# Silicoin.net
KiCad netlist of a schematic drawn in EAGLE
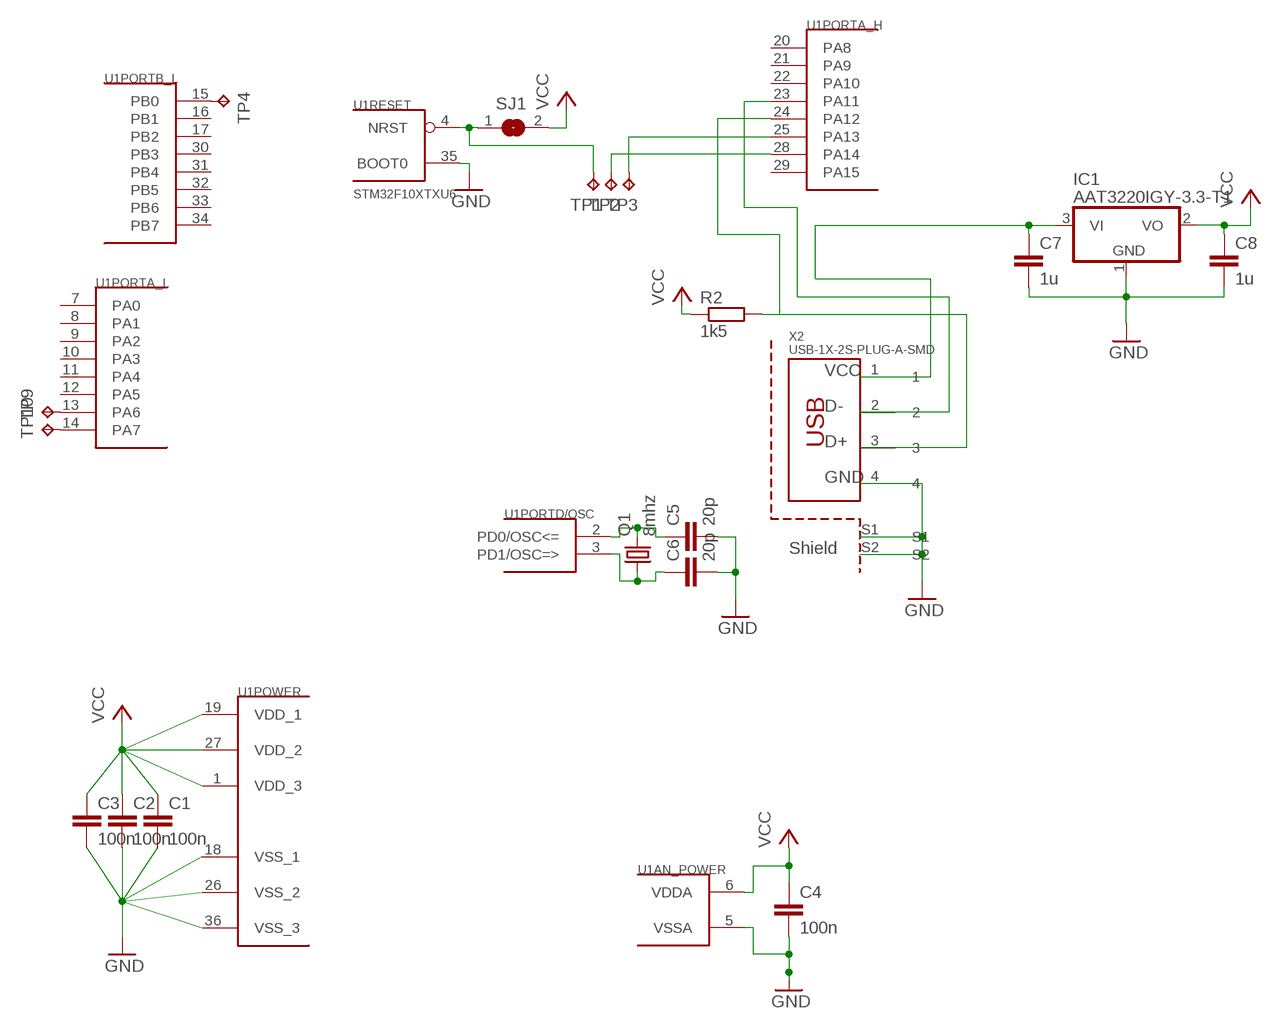
[diagram p0: schematic, sheet 1]

(export (version "E")
  (design (tool "Eeschema 10.0.6"))
  (components
    (comp (ref "C1")
      (value "100n")
      (footprint "eagle-import:C0603")
      (libsource (lib "eagle-import") (part "C-EUC0603"))
    )
    (comp (ref "C2")
      (value "100n")
      (footprint "eagle-import:C0603")
      (libsource (lib "eagle-import") (part "C-EUC0603"))
    )
    (comp (ref "C3")
      (value "100n")
      (footprint "eagle-import:C0603")
      (libsource (lib "eagle-import") (part "C-EUC0603"))
    )
    (comp (ref "C4")
      (value "100n")
      (footprint "eagle-import:C0603")
      (libsource (lib "eagle-import") (part "C-EUC0603"))
    )
    (comp (ref "C5")
      (value "20p")
      (footprint "eagle-import:C0603")
      (libsource (lib "eagle-import") (part "C-EUC0603"))
    )
    (comp (ref "C6")
      (value "20p")
      (footprint "eagle-import:C0603")
      (libsource (lib "eagle-import") (part "C-EUC0603"))
    )
    (comp (ref "C7")
      (value "1u")
      (footprint "eagle-import:C0603")
      (libsource (lib "eagle-import") (part "C-EUC0603"))
    )
    (comp (ref "C8")
      (value "1u")
      (footprint "eagle-import:C0603")
      (libsource (lib "eagle-import") (part "C-EUC0603"))
    )
    (comp (ref "IC1")
      (value "AAT3220IGY-3.3-T1")
      (footprint "eagle-import:SOT23")
      (libsource (lib "eagle-import") (part "MCP1703CB"))
    )
    (comp (ref "Q1")
      (value "8mhz")
      (footprint "eagle-import:CSM-7X-DU")
      (libsource (lib "eagle-import") (part "CSM-7X-DU"))
    )
    (comp (ref "R2")
      (value "1k5")
      (footprint "eagle-import:R0603")
      (libsource (lib "eagle-import") (part "R-EU_R0603"))
    )
    (comp (ref "SJ1") (value "SJ") (footprint "eagle-import:SJ") (libsource (lib "eagle-import") (part "SJ")))
    (comp (ref "TP1")
      (value "TPB2,54")
      (footprint "eagle-import:B2,54")
      (libsource (lib "eagle-import") (part "TPB2,54"))
    )
    (comp (ref "TP2")
      (value "TPB2,54")
      (footprint "eagle-import:B2,54")
      (libsource (lib "eagle-import") (part "TPB2,54"))
    )
    (comp (ref "TP3")
      (value "TPB2,54")
      (footprint "eagle-import:B2,54")
      (libsource (lib "eagle-import") (part "TPB2,54"))
    )
    (comp (ref "TP4")
      (value "TPB2,54")
      (footprint "eagle-import:B2,54")
      (libsource (lib "eagle-import") (part "TPB2,54"))
    )
    (comp (ref "TP9")
      (value "TPB2,54")
      (footprint "eagle-import:B2,54")
      (libsource (lib "eagle-import") (part "TPB2,54"))
    )
    (comp (ref "TP10")
      (value "TPB2,54")
      (footprint "eagle-import:B2,54")
      (libsource (lib "eagle-import") (part "TPB2,54"))
    )
    (comp (ref "U1")
      (value "STM32F10XTXU6")
      (footprint "eagle-import:VFQFPN36")
      (libsource (lib "eagle-import") (part "STM32F10XTXU6"))
    )
    (comp (ref "X2")
      (value "USB-1X-2S-PLUG-A-SMD")
      (footprint "eagle-import:USB-PLUG-A-SMD-2S")
      (libsource (lib "eagle-import") (part "USB-1X-2S-PLUG-A-SMD"))
    )
  )
  (nets
    (net (code "1") (name "GND") (class "Default")
      (node (ref "C1") (pin "2") (pinfunction "2_2") (pintype "passive"))
      (node (ref "C2") (pin "2") (pinfunction "2_2") (pintype "passive"))
      (node (ref "C3") (pin "2") (pinfunction "2_2") (pintype "passive"))
      (node (ref "C4") (pin "2") (pinfunction "2_2") (pintype "passive"))
      (node (ref "C5") (pin "2") (pinfunction "2_2") (pintype "passive"))
      (node (ref "C6") (pin "2") (pinfunction "2_2") (pintype "passive"))
      (node (ref "C7") (pin "2") (pinfunction "2_2") (pintype "passive"))
      (node (ref "C8") (pin "2") (pinfunction "2_2") (pintype "passive"))
      (node (ref "IC1") (pin "1") (pinfunction "GND_1") (pintype "passive"))
      (node (ref "U1") (pin "18") (pinfunction "VSS_1_18") (pintype "power_in"))
      (node (ref "U1") (pin "26") (pinfunction "VSS_2_26") (pintype "power_in"))
      (node (ref "U1") (pin "35") (pinfunction "BOOT0_35") (pintype "input"))
      (node (ref "U1") (pin "36") (pinfunction "VSS_3_36") (pintype "power_in"))
      (node (ref "U1") (pin "5") (pinfunction "VSSA_5") (pintype "power_in"))
      (node (ref "X2") (pin "4") (pinfunction "4_4") (pintype "passive"))
      (node (ref "X2") (pin "S1") (pinfunction "S1_S1") (pintype "passive"))
      (node (ref "X2") (pin "S2") (pinfunction "S2_S2") (pintype "passive"))
    )
    (net (code "2") (name "Net-(IC1-VI)") (class "Default")
      (node (ref "C7") (pin "1") (pinfunction "1_1") (pintype "passive"))
      (node (ref "IC1") (pin "3") (pinfunction "VI_3") (pintype "input"))
      (node (ref "X2") (pin "1") (pinfunction "1_1") (pintype "passive"))
    )
    (net (code "3") (name "Net-(U1B-PA11)") (class "Default")
      (node (ref "U1") (pin "23") (pinfunction "PA11_23") (pintype "bidirectional"))
      (node (ref "X2") (pin "2") (pinfunction "2_2") (pintype "passive"))
    )
    (net (code "4") (name "Net-(U1B-PA12)") (class "Default")
      (node (ref "R2") (pin "2") (pinfunction "2_2") (pintype "passive"))
      (node (ref "U1") (pin "24") (pinfunction "PA12_24") (pintype "bidirectional"))
      (node (ref "X2") (pin "3") (pinfunction "3_3") (pintype "passive"))
    )
    (net (code "5") (name "Net-(U1B-PA13)") (class "Default")
      (node (ref "TP3") (pin "TP") (pinfunction "TP_TP") (pintype "input"))
      (node (ref "U1") (pin "25") (pinfunction "PA13_25") (pintype "bidirectional"))
    )
    (net (code "6") (name "Net-(U1B-PA14)") (class "Default")
      (node (ref "TP2") (pin "TP") (pinfunction "TP_TP") (pintype "input"))
      (node (ref "U1") (pin "28") (pinfunction "PA14_28") (pintype "bidirectional"))
    )
    (net (code "7") (name "Net-(U1C-PA6)") (class "Default")
      (node (ref "TP9") (pin "TP") (pinfunction "TP_TP") (pintype "input"))
      (node (ref "U1") (pin "13") (pinfunction "PA6_13") (pintype "bidirectional"))
    )
    (net (code "8") (name "Net-(U1C-PA7)") (class "Default")
      (node (ref "TP10") (pin "TP") (pinfunction "TP_TP") (pintype "input"))
      (node (ref "U1") (pin "14") (pinfunction "PA7_14") (pintype "bidirectional"))
    )
    (net (code "9") (name "Net-(U1D-PB0)") (class "Default")
      (node (ref "TP4") (pin "TP") (pinfunction "TP_TP") (pintype "input"))
      (node (ref "U1") (pin "15") (pinfunction "PB0_15") (pintype "bidirectional"))
    )
    (net (code "10") (name "Net-(U1E-PD0{slash}OSC<=)") (class "Default")
      (node (ref "C5") (pin "1") (pinfunction "1_1") (pintype "passive"))
      (node (ref "Q1") (pin "2") (pinfunction "2_2") (pintype "passive"))
      (node (ref "U1") (pin "2") (pinfunction "PD0/OSC<=_2") (pintype "bidirectional"))
    )
    (net (code "11") (name "Net-(U1E-PD1{slash}OSC=>)") (class "Default")
      (node (ref "C6") (pin "1") (pinfunction "1_1") (pintype "passive"))
      (node (ref "Q1") (pin "1") (pinfunction "1_1") (pintype "passive"))
      (node (ref "U1") (pin "3") (pinfunction "PD1/OSC=>_3") (pintype "bidirectional"))
    )
    (net (code "12") (name "Net-(U1G-NRST)") (class "Default")
      (node (ref "SJ1") (pin "1") (pinfunction "1_1") (pintype "passive"))
      (node (ref "TP1") (pin "TP") (pinfunction "TP_TP") (pintype "input"))
      (node (ref "U1") (pin "4") (pinfunction "NRST_4") (pintype "input"))
    )
    (net (code "13") (name "VCC") (class "Default")
      (node (ref "C1") (pin "1") (pinfunction "1_1") (pintype "passive"))
      (node (ref "C2") (pin "1") (pinfunction "1_1") (pintype "passive"))
      (node (ref "C3") (pin "1") (pinfunction "1_1") (pintype "passive"))
      (node (ref "C4") (pin "1") (pinfunction "1_1") (pintype "passive"))
      (node (ref "C8") (pin "1") (pinfunction "1_1") (pintype "passive"))
      (node (ref "IC1") (pin "2") (pinfunction "VO_2") (pintype "passive"))
      (node (ref "R2") (pin "1") (pinfunction "1_1") (pintype "passive"))
      (node (ref "SJ1") (pin "2") (pinfunction "2_2") (pintype "passive"))
      (node (ref "U1") (pin "1") (pinfunction "VDD_3_1") (pintype "power_in"))
      (node (ref "U1") (pin "19") (pinfunction "VDD_1_19") (pintype "power_in"))
      (node (ref "U1") (pin "27") (pinfunction "VDD_2_27") (pintype "power_in"))
      (node (ref "U1") (pin "6") (pinfunction "VDDA_6") (pintype "power_in"))
    )
    (net (code "14") (name "unconnected-(U1B-PA8-Pad20)") (class "Default")
      (node (ref "U1") (pin "20") (pinfunction "PA8_20") (pintype "bidirectional"))
    )
    (net (code "15") (name "unconnected-(U1B-PA9-Pad21)") (class "Default")
      (node (ref "U1") (pin "21") (pinfunction "PA9_21") (pintype "bidirectional"))
    )
    (net (code "16") (name "unconnected-(U1B-PA10-Pad22)") (class "Default")
      (node (ref "U1") (pin "22") (pinfunction "PA10_22") (pintype "bidirectional"))
    )
    (net (code "17") (name "unconnected-(U1B-PA15-Pad29)") (class "Default")
      (node (ref "U1") (pin "29") (pinfunction "PA15_29") (pintype "bidirectional"))
    )
    (net (code "18") (name "unconnected-(U1C-PA0-Pad7)") (class "Default")
      (node (ref "U1") (pin "7") (pinfunction "PA0_7") (pintype "bidirectional"))
    )
    (net (code "19") (name "unconnected-(U1C-PA1-Pad8)") (class "Default")
      (node (ref "U1") (pin "8") (pinfunction "PA1_8") (pintype "bidirectional"))
    )
    (net (code "20") (name "unconnected-(U1C-PA2-Pad9)") (class "Default")
      (node (ref "U1") (pin "9") (pinfunction "PA2_9") (pintype "bidirectional"))
    )
    (net (code "21") (name "unconnected-(U1C-PA3-Pad10)") (class "Default")
      (node (ref "U1") (pin "10") (pinfunction "PA3_10") (pintype "bidirectional"))
    )
    (net (code "22") (name "unconnected-(U1C-PA4-Pad11)") (class "Default")
      (node (ref "U1") (pin "11") (pinfunction "PA4_11") (pintype "bidirectional"))
    )
    (net (code "23") (name "unconnected-(U1C-PA5-Pad12)") (class "Default")
      (node (ref "U1") (pin "12") (pinfunction "PA5_12") (pintype "bidirectional"))
    )
    (net (code "24") (name "unconnected-(U1D-PB1-Pad16)") (class "Default")
      (node (ref "U1") (pin "16") (pinfunction "PB1_16") (pintype "bidirectional"))
    )
    (net (code "25") (name "unconnected-(U1D-PB2-Pad17)") (class "Default")
      (node (ref "U1") (pin "17") (pinfunction "PB2_17") (pintype "bidirectional"))
    )
    (net (code "26") (name "unconnected-(U1D-PB3-Pad30)") (class "Default")
      (node (ref "U1") (pin "30") (pinfunction "PB3_30") (pintype "bidirectional"))
    )
    (net (code "27") (name "unconnected-(U1D-PB4-Pad31)") (class "Default")
      (node (ref "U1") (pin "31") (pinfunction "PB4_31") (pintype "bidirectional"))
    )
    (net (code "28") (name "unconnected-(U1D-PB5-Pad32)") (class "Default")
      (node (ref "U1") (pin "32") (pinfunction "PB5_32") (pintype "bidirectional"))
    )
    (net (code "29") (name "unconnected-(U1D-PB6-Pad33)") (class "Default")
      (node (ref "U1") (pin "33") (pinfunction "PB6_33") (pintype "bidirectional"))
    )
    (net (code "30") (name "unconnected-(U1D-PB7-Pad34)") (class "Default")
      (node (ref "U1") (pin "34") (pinfunction "PB7_34") (pintype "bidirectional"))
    )
  )
)
